# Analog_-_Low_Speed_SE.net
KiCad netlist of a schematic drawn in Altium Designer
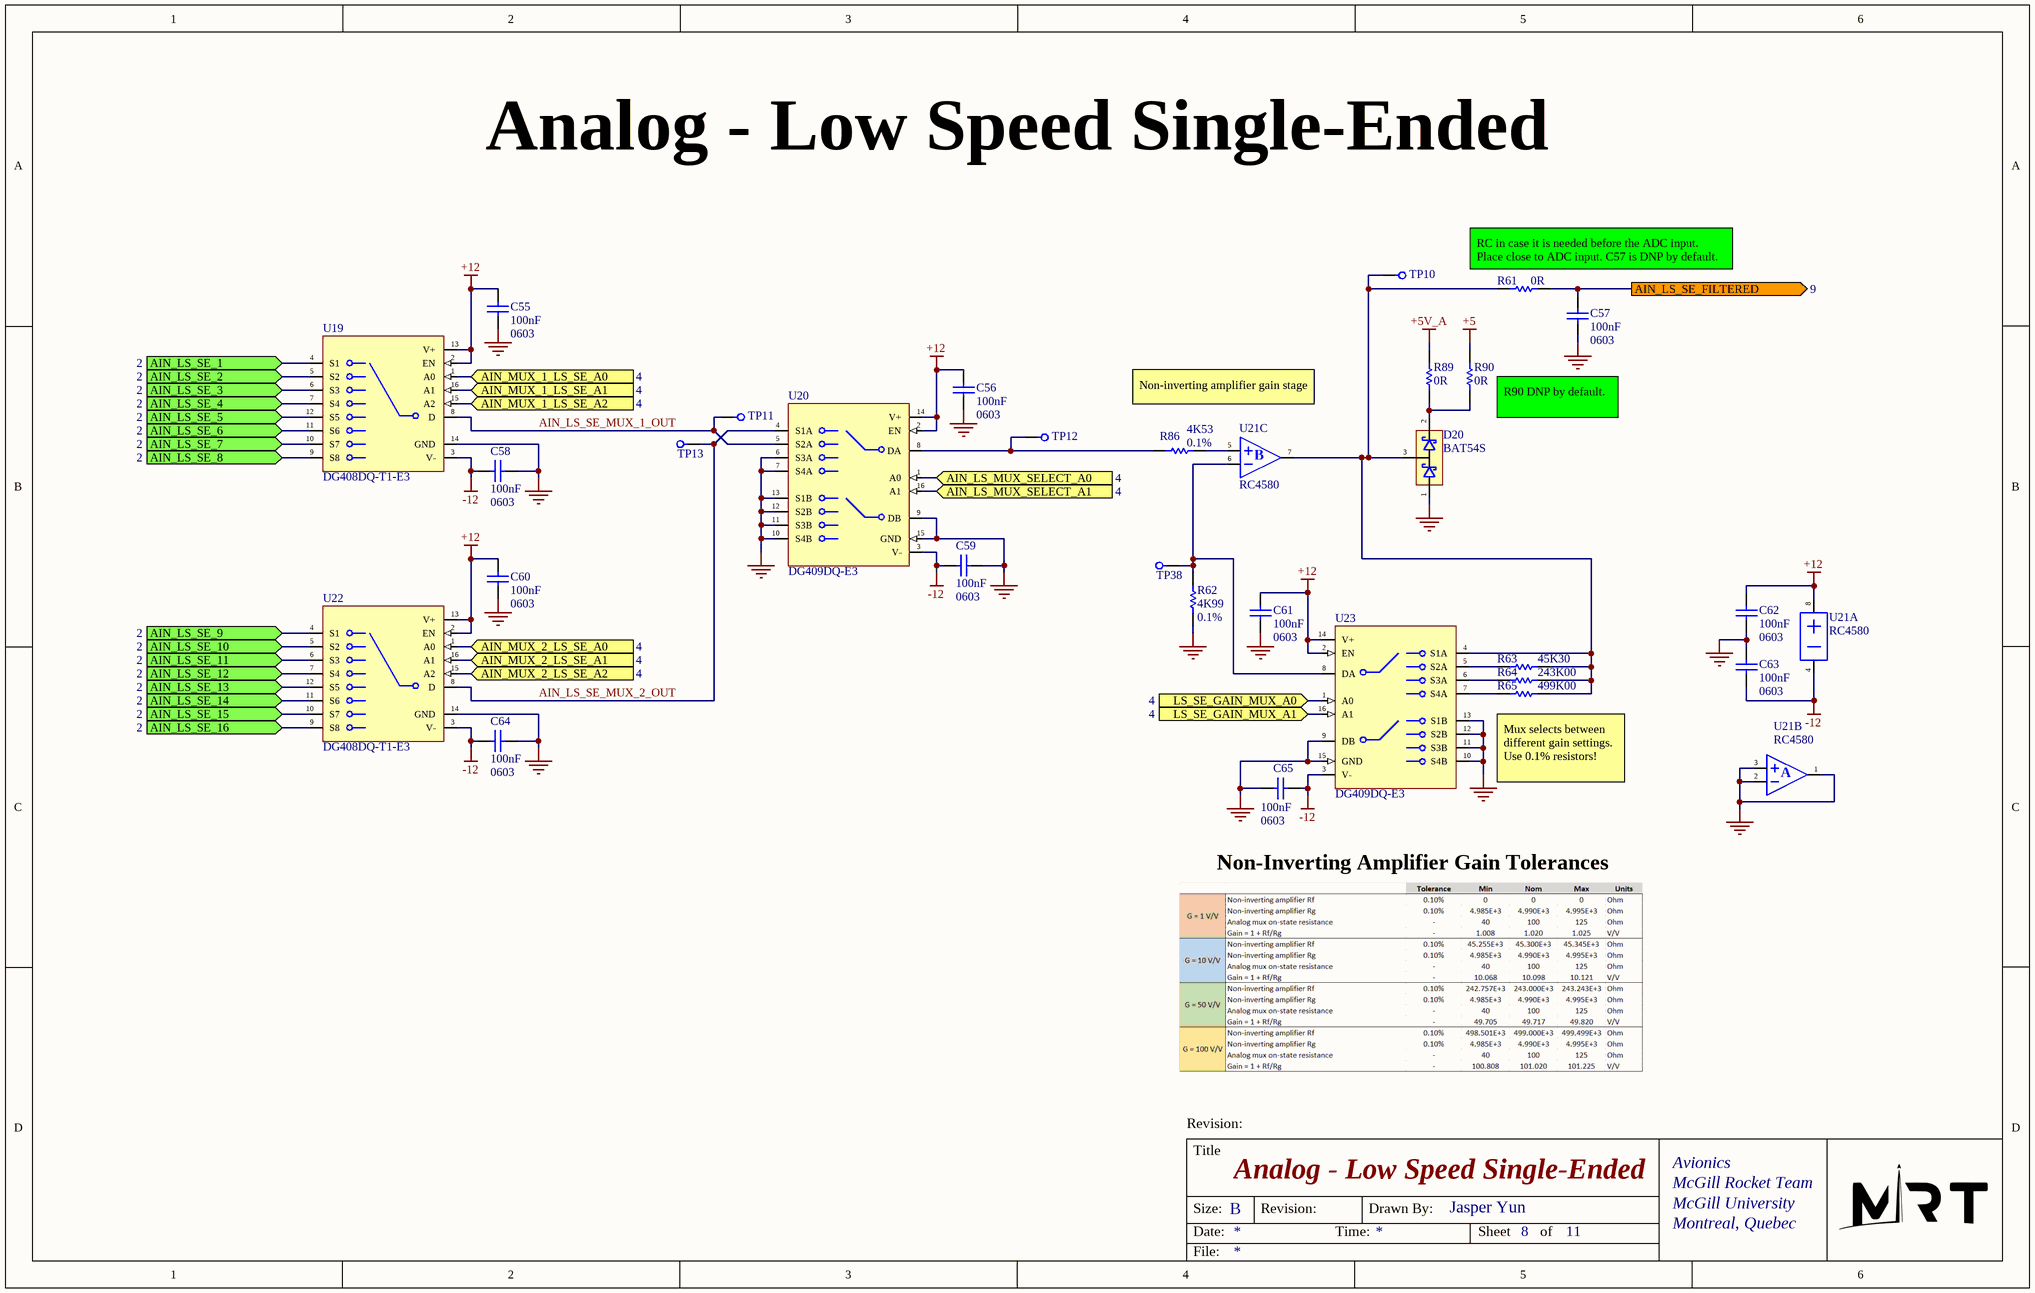
[diagram p0: Analog - Low Speed SE.SchDoc]

(export (version "E")
  (design (tool "Eeschema 10.0.6"))
  (components
    (comp (ref "C55")
      (value "100nF")
      (footprint "0603 CAP SAMSUNG CL10C")
      (description "Capacitor")
      (fields (field (name "ALTIUM_VALUE") "0603") (field (name "PUBLISHER") "Altium Limited"))
      (libsource (lib "Miscellaneous Devices") (part "Cap"))
    )
    (comp (ref "C56")
      (value "100nF")
      (footprint "0603 CAP SAMSUNG CL10C")
      (description "Capacitor")
      (fields (field (name "ALTIUM_VALUE") "0603") (field (name "PUBLISHER") "Altium Limited"))
      (libsource (lib "Miscellaneous Devices") (part "Cap"))
    )
    (comp (ref "C57")
      (value "100nF")
      (footprint "0603 CAP SAMSUNG CL10C")
      (description "Capacitor")
      (fields (field (name "ALTIUM_VALUE") "0603") (field (name "PUBLISHER") "Altium Limited"))
      (libsource (lib "Miscellaneous Devices") (part "Cap"))
    )
    (comp (ref "C58")
      (value "100nF")
      (footprint "0603 CAP SAMSUNG CL10C")
      (description "Capacitor")
      (fields (field (name "ALTIUM_VALUE") "0603") (field (name "PUBLISHER") "Altium Limited"))
      (libsource (lib "Miscellaneous Devices") (part "Cap"))
    )
    (comp (ref "C59")
      (value "100nF")
      (footprint "0603 CAP SAMSUNG CL10C")
      (description "Capacitor")
      (fields (field (name "ALTIUM_VALUE") "0603") (field (name "PUBLISHER") "Altium Limited"))
      (libsource (lib "Miscellaneous Devices") (part "Cap"))
    )
    (comp (ref "C60")
      (value "100nF")
      (footprint "0603 CAP SAMSUNG CL10C")
      (description "Capacitor")
      (fields (field (name "ALTIUM_VALUE") "0603") (field (name "PUBLISHER") "Altium Limited"))
      (libsource (lib "Miscellaneous Devices") (part "Cap"))
    )
    (comp (ref "C61")
      (value "100nF")
      (footprint "0603 CAP SAMSUNG CL10C")
      (description "Capacitor")
      (fields (field (name "ALTIUM_VALUE") "0603") (field (name "PUBLISHER") "Altium Limited"))
      (libsource (lib "Miscellaneous Devices") (part "Cap"))
    )
    (comp (ref "C62")
      (value "100nF")
      (footprint "0603 CAP SAMSUNG CL10C")
      (description "Capacitor")
      (fields (field (name "ALTIUM_VALUE") "0603") (field (name "PUBLISHER") "Altium Limited"))
      (libsource (lib "Miscellaneous Devices") (part "Cap"))
    )
    (comp (ref "C63")
      (value "100nF")
      (footprint "0603 CAP SAMSUNG CL10C")
      (description "Capacitor")
      (fields (field (name "ALTIUM_VALUE") "0603") (field (name "PUBLISHER") "Altium Limited"))
      (libsource (lib "Miscellaneous Devices") (part "Cap"))
    )
    (comp (ref "C64")
      (value "100nF")
      (footprint "0603 CAP SAMSUNG CL10C")
      (description "Capacitor")
      (fields (field (name "ALTIUM_VALUE") "0603") (field (name "PUBLISHER") "Altium Limited"))
      (libsource (lib "Miscellaneous Devices") (part "Cap"))
    )
    (comp (ref "C65")
      (value "100nF")
      (footprint "0603 CAP SAMSUNG CL10C")
      (description "Capacitor")
      (fields (field (name "ALTIUM_VALUE") "0603") (field (name "PUBLISHER") "Altium Limited"))
      (libsource (lib "Miscellaneous Devices") (part "Cap"))
    )
    (comp (ref "D20")
      (value "BAT54S")
      (footprint "SOT23-3")
      (description "Rectifier Diode Small Signal Schottky 40V 0.3A 5ns 3-Pin SOT-23 T/R")
      (fields
        (field (name "MANUFACTURER") "STMicroelectronics")
        (field (name "MANUFACTURER PART NUMBER") "BAT54SFILM")
      )
      (libsource (lib "MRT SCH Library") (part "Schottky Diode Array BAT54S"))
    )
    (comp (ref "R61")
      (value "0R")
      (footprint "0603 RES")
      (description "Resistor")
      (fields (field (name "PUBLISHER") "Altium Limited"))
      (libsource (lib "Miscellaneous Devices") (part "Res1"))
    )
    (comp (ref "R62")
      (value "4K99")
      (footprint "0603 RES")
      (description "Resistor")
      (fields (field (name "ALTIUM_VALUE") "0.1%") (field (name "PUBLISHER") "Altium Limited"))
      (libsource (lib "Miscellaneous Devices") (part "Res1"))
    )
    (comp (ref "R63")
      (value "45K30")
      (footprint "0603 RES")
      (description "Resistor")
      (fields (field (name "PUBLISHER") "Altium Limited"))
      (libsource (lib "Miscellaneous Devices") (part "Res1"))
    )
    (comp (ref "R64")
      (value "243K00")
      (footprint "0603 RES")
      (description "Resistor")
      (fields (field (name "PUBLISHER") "Altium Limited"))
      (libsource (lib "Miscellaneous Devices") (part "Res1"))
    )
    (comp (ref "R65")
      (value "499K00")
      (footprint "0603 RES")
      (description "Resistor")
      (fields (field (name "PUBLISHER") "Altium Limited"))
      (libsource (lib "Miscellaneous Devices") (part "Res1"))
    )
    (comp (ref "R86")
      (value "4K53")
      (footprint "0603 RES")
      (description "Resistor")
      (fields (field (name "ALTIUM_VALUE") "0.1%") (field (name "PUBLISHER") "Altium Limited"))
      (libsource (lib "Miscellaneous Devices") (part "Res1"))
    )
    (comp (ref "R89")
      (value "0R")
      (footprint "0603 RES")
      (description "Resistor")
      (fields (field (name "PUBLISHER") "Altium Limited"))
      (libsource (lib "Miscellaneous Devices") (part "Res1"))
    )
    (comp (ref "R90")
      (value "0R")
      (footprint "0603 RES")
      (description "Resistor")
      (fields (field (name "PUBLISHER") "Altium Limited"))
      (libsource (lib "Miscellaneous Devices") (part "Res1"))
    )
    (comp (ref "TP10")
      (value "Test Point")
      (footprint "Test Point Keystone 5015")
      (description "Keystone 5015 Test point")
      (libsource (lib "MRT SCH Library") (part "Test Point"))
    )
    (comp (ref "TP11")
      (value "Test Point")
      (footprint "TEST POINT SMD PAD")
      (description "Keystone 5015 Test point")
      (libsource (lib "MRT SCH Library") (part "Test Point"))
    )
    (comp (ref "TP12")
      (value "Test Point")
      (footprint "Test Point Keystone 5015")
      (description "Keystone 5015 Test point")
      (libsource (lib "MRT SCH Library") (part "Test Point"))
    )
    (comp (ref "TP13")
      (value "Test Point")
      (footprint "TEST POINT SMD PAD")
      (description "Keystone 5015 Test point")
      (libsource (lib "MRT SCH Library") (part "Test Point"))
    )
    (comp (ref "TP38")
      (value "Test Point")
      (footprint "Test Point Keystone 5015")
      (description "Keystone 5015 Test point")
      (libsource (lib "MRT SCH Library") (part "Test Point"))
    )
    (comp (ref "U19")
      (value "DG408DQ-T1-E3")
      (footprint "TSSOP-16")
      (description "DG408DQ-T1-E3; Multiplexer Single 8: 1; 15 V; 18 V; 24 V; 28 V; 16-Pin TSSOP")
      (fields (field (name "MANUFACTURER") "Vishay Siliconix"))
      (libsource (lib "MRT SCH Library") (part "Analog Mux DG408DQ-T1-E3"))
    )
    (comp (ref "U20")
      (value "DG409DQ-E3")
      (footprint "TSSOP-16")
      (description "DG409 Series 20 V 8-Ch/Dual 4-Ch High-Performance CMOS Analog Multiplexer")
      (fields (field (name "MANUFACTURER") "Vishay Siliconix"))
      (libsource (lib "") (part "Analog Mux DG409DQ-E3_1"))
    )
    (comp (ref "U21")
      (value "RC4580")
      (footprint "SOIC-8")
      (fields
        (field (name "MANUFACTURER") "Texas Instruments")
        (field (name "MANUFACTURER PART NUMBER") "RC4580IDR")
      )
      (libsource (lib "MRT SCH Library") (part "OP AMP RC4580"))
    )
    (comp (ref "U22")
      (value "DG408DQ-T1-E3")
      (footprint "TSSOP-16")
      (description "DG408DQ-T1-E3; Multiplexer Single 8: 1; 15 V; 18 V; 24 V; 28 V; 16-Pin TSSOP")
      (fields (field (name "MANUFACTURER") "Vishay Siliconix"))
      (libsource (lib "MRT SCH Library") (part "Analog Mux DG408DQ-T1-E3"))
    )
    (comp (ref "U23")
      (value "DG409DQ-E3")
      (footprint "TSSOP-16")
      (description "DG409 Series 20 V 8-Ch/Dual 4-Ch High-Performance CMOS Analog Multiplexer")
      (fields (field (name "MANUFACTURER") "Vishay Siliconix"))
      (libsource (lib "MRT SCH Library") (part "Analog Mux DG409DQ-E3"))
    )
  )
  (nets
    (net (code "1") (name "+5") (class "Default")
      (node (ref "R90") (pin "1") (pinfunction "1_1") (pintype "passive"))
    )
    (net (code "2") (name "+5V_A") (class "Default")
      (node (ref "R89") (pin "1") (pinfunction "1_1") (pintype "passive"))
    )
    (net (code "3") (name "+12") (class "Default")
      (node (ref "C55") (pin "2") (pinfunction "2_2") (pintype "passive"))
      (node (ref "C56") (pin "2") (pinfunction "2_2") (pintype "passive"))
      (node (ref "C60") (pin "2") (pinfunction "2_2") (pintype "passive"))
      (node (ref "C61") (pin "2") (pinfunction "2_2") (pintype "passive"))
      (node (ref "C62") (pin "2") (pinfunction "2_2") (pintype "passive"))
      (node (ref "U19") (pin "13") (pinfunction "V+_13") (pintype "passive"))
      (node (ref "U19") (pin "2") (pinfunction "EN_2") (pintype "input"))
      (node (ref "U20") (pin "14") (pinfunction "V+_14") (pintype "passive"))
      (node (ref "U20") (pin "2") (pinfunction "EN_2") (pintype "input"))
      (node (ref "U21") (pin "8") (pinfunction "VCC+_8") (pintype "passive"))
      (node (ref "U22") (pin "13") (pinfunction "V+_13") (pintype "passive"))
      (node (ref "U22") (pin "2") (pinfunction "EN_2") (pintype "input"))
      (node (ref "U23") (pin "14") (pinfunction "V+_14") (pintype "passive"))
      (node (ref "U23") (pin "2") (pinfunction "EN_2") (pintype "input"))
    )
    (net (code "4") (name "-12") (class "Default")
      (node (ref "C58") (pin "2") (pinfunction "2_2") (pintype "passive"))
      (node (ref "C59") (pin "2") (pinfunction "2_2") (pintype "passive"))
      (node (ref "C63") (pin "1") (pinfunction "1_1") (pintype "passive"))
      (node (ref "C64") (pin "2") (pinfunction "2_2") (pintype "passive"))
      (node (ref "C65") (pin "2") (pinfunction "2_2") (pintype "passive"))
      (node (ref "U19") (pin "3") (pinfunction "V-_3") (pintype "passive"))
      (node (ref "U20") (pin "3") (pinfunction "V-_3") (pintype "passive"))
      (node (ref "U21") (pin "4") (pinfunction "VCC-_4") (pintype "passive"))
      (node (ref "U22") (pin "3") (pinfunction "V-_3") (pintype "passive"))
      (node (ref "U23") (pin "3") (pinfunction "V-_3") (pintype "passive"))
    )
    (net (code "5") (name "/AIN_LS_MUX_SELECT_A0") (class "Default")
      (node (ref "U20") (pin "1") (pinfunction "A0_1") (pintype "input"))
    )
    (net (code "6") (name "/AIN_LS_MUX_SELECT_A1") (class "Default")
      (node (ref "U20") (pin "16") (pinfunction "A1_16") (pintype "input"))
    )
    (net (code "7") (name "/AIN_LS_SE_1") (class "Default")
      (node (ref "U19") (pin "4") (pinfunction "S1_4") (pintype "passive"))
    )
    (net (code "8") (name "/AIN_LS_SE_2") (class "Default")
      (node (ref "U19") (pin "5") (pinfunction "S2_5") (pintype "passive"))
    )
    (net (code "9") (name "/AIN_LS_SE_3") (class "Default")
      (node (ref "U19") (pin "6") (pinfunction "S3_6") (pintype "passive"))
    )
    (net (code "10") (name "/AIN_LS_SE_4") (class "Default")
      (node (ref "U19") (pin "7") (pinfunction "S4_7") (pintype "passive"))
    )
    (net (code "11") (name "/AIN_LS_SE_5") (class "Default")
      (node (ref "U19") (pin "12") (pinfunction "S5_12") (pintype "passive"))
    )
    (net (code "12") (name "/AIN_LS_SE_6") (class "Default")
      (node (ref "U19") (pin "11") (pinfunction "S6_11") (pintype "passive"))
    )
    (net (code "13") (name "/AIN_LS_SE_7") (class "Default")
      (node (ref "U19") (pin "10") (pinfunction "S7_10") (pintype "passive"))
    )
    (net (code "14") (name "/AIN_LS_SE_8") (class "Default")
      (node (ref "U19") (pin "9") (pinfunction "S8_9") (pintype "passive"))
    )
    (net (code "15") (name "/AIN_LS_SE_9") (class "Default")
      (node (ref "U22") (pin "4") (pinfunction "S1_4") (pintype "passive"))
    )
    (net (code "16") (name "/AIN_LS_SE_10") (class "Default")
      (node (ref "U22") (pin "5") (pinfunction "S2_5") (pintype "passive"))
    )
    (net (code "17") (name "/AIN_LS_SE_11") (class "Default")
      (node (ref "U22") (pin "6") (pinfunction "S3_6") (pintype "passive"))
    )
    (net (code "18") (name "/AIN_LS_SE_12") (class "Default")
      (node (ref "U22") (pin "7") (pinfunction "S4_7") (pintype "passive"))
    )
    (net (code "19") (name "/AIN_LS_SE_13") (class "Default")
      (node (ref "U22") (pin "12") (pinfunction "S5_12") (pintype "passive"))
    )
    (net (code "20") (name "/AIN_LS_SE_14") (class "Default")
      (node (ref "U22") (pin "11") (pinfunction "S6_11") (pintype "passive"))
    )
    (net (code "21") (name "/AIN_LS_SE_15") (class "Default")
      (node (ref "U22") (pin "10") (pinfunction "S7_10") (pintype "passive"))
    )
    (net (code "22") (name "/AIN_LS_SE_16") (class "Default")
      (node (ref "U22") (pin "9") (pinfunction "S8_9") (pintype "passive"))
    )
    (net (code "23") (name "/AIN_LS_SE_FILTERED") (class "Default")
      (node (ref "C57") (pin "2") (pinfunction "2_2") (pintype "passive"))
      (node (ref "R61") (pin "1") (pinfunction "1_1") (pintype "passive"))
    )
    (net (code "24") (name "/AIN_LS_SE_MUX_1_OUT") (class "Default")
      (node (ref "TP11") (pin "1") (pinfunction "1_1") (pintype "passive"))
      (node (ref "U19") (pin "8") (pinfunction "D_8") (pintype "passive"))
      (node (ref "U20") (pin "5") (pinfunction "S2A_5") (pintype "passive"))
    )
    (net (code "25") (name "/AIN_LS_SE_MUX_2_OUT") (class "Default")
      (node (ref "TP13") (pin "1") (pinfunction "1_1") (pintype "passive"))
      (node (ref "U20") (pin "4") (pinfunction "S1A_4") (pintype "passive"))
      (node (ref "U22") (pin "8") (pinfunction "D_8") (pintype "passive"))
    )
    (net (code "26") (name "/AIN_MUX_1_LS_SE_A0") (class "Default")
      (node (ref "U19") (pin "1") (pinfunction "A0_1") (pintype "input"))
    )
    (net (code "27") (name "/AIN_MUX_1_LS_SE_A1") (class "Default")
      (node (ref "U19") (pin "16") (pinfunction "A1_16") (pintype "input"))
    )
    (net (code "28") (name "/AIN_MUX_1_LS_SE_A2") (class "Default")
      (node (ref "U19") (pin "15") (pinfunction "A2_15") (pintype "input"))
    )
    (net (code "29") (name "/AIN_MUX_2_LS_SE_A0") (class "Default")
      (node (ref "U22") (pin "1") (pinfunction "A0_1") (pintype "input"))
    )
    (net (code "30") (name "/AIN_MUX_2_LS_SE_A1") (class "Default")
      (node (ref "U22") (pin "16") (pinfunction "A1_16") (pintype "input"))
    )
    (net (code "31") (name "/AIN_MUX_2_LS_SE_A2") (class "Default")
      (node (ref "U22") (pin "15") (pinfunction "A2_15") (pintype "input"))
    )
    (net (code "32") (name "/LS_SE_GAIN_MUX_A0") (class "Default")
      (node (ref "U23") (pin "1") (pinfunction "A0_1") (pintype "input"))
    )
    (net (code "33") (name "/LS_SE_GAIN_MUX_A1") (class "Default")
      (node (ref "U23") (pin "16") (pinfunction "A1_16") (pintype "input"))
    )
    (net (code "34") (name "GND") (class "Default")
      (node (ref "C55") (pin "1") (pinfunction "1_1") (pintype "passive"))
      (node (ref "C56") (pin "1") (pinfunction "1_1") (pintype "passive"))
      (node (ref "C57") (pin "1") (pinfunction "1_1") (pintype "passive"))
      (node (ref "C58") (pin "1") (pinfunction "1_1") (pintype "passive"))
      (node (ref "C59") (pin "1") (pinfunction "1_1") (pintype "passive"))
      (node (ref "C60") (pin "1") (pinfunction "1_1") (pintype "passive"))
      (node (ref "C61") (pin "1") (pinfunction "1_1") (pintype "passive"))
      (node (ref "C62") (pin "1") (pinfunction "1_1") (pintype "passive"))
      (node (ref "C63") (pin "2") (pinfunction "2_2") (pintype "passive"))
      (node (ref "C64") (pin "1") (pinfunction "1_1") (pintype "passive"))
      (node (ref "C65") (pin "1") (pinfunction "1_1") (pintype "passive"))
      (node (ref "D20") (pin "1") (pinfunction "1_1") (pintype "passive"))
      (node (ref "R62") (pin "1") (pinfunction "1_1") (pintype "passive"))
      (node (ref "U19") (pin "14") (pinfunction "GND_14") (pintype "passive"))
      (node (ref "U20") (pin "10") (pinfunction "S4B_10") (pintype "passive"))
      (node (ref "U20") (pin "11") (pinfunction "S3B_11") (pintype "passive"))
      (node (ref "U20") (pin "12") (pinfunction "S2B_12") (pintype "passive"))
      (node (ref "U20") (pin "13") (pinfunction "S1B_13") (pintype "passive"))
      (node (ref "U20") (pin "15") (pinfunction "GND_15") (pintype "input"))
      (node (ref "U20") (pin "6") (pinfunction "S3A_6") (pintype "passive"))
      (node (ref "U20") (pin "7") (pinfunction "S4A_7") (pintype "passive"))
      (node (ref "U20") (pin "9") (pinfunction "DB_9") (pintype "passive"))
      (node (ref "U21") (pin "1") (pinfunction "1_1") (pintype "passive"))
      (node (ref "U21") (pin "2") (pinfunction "2_2") (pintype "passive"))
      (node (ref "U21") (pin "3") (pinfunction "3_3") (pintype "passive"))
      (node (ref "U22") (pin "14") (pinfunction "GND_14") (pintype "passive"))
      (node (ref "U23") (pin "10") (pinfunction "S4B_10") (pintype "passive"))
      (node (ref "U23") (pin "11") (pinfunction "S3B_11") (pintype "passive"))
      (node (ref "U23") (pin "12") (pinfunction "S2B_12") (pintype "passive"))
      (node (ref "U23") (pin "13") (pinfunction "S1B_13") (pintype "passive"))
      (node (ref "U23") (pin "15") (pinfunction "GND_15") (pintype "input"))
      (node (ref "U23") (pin "9") (pinfunction "DB_9") (pintype "passive"))
    )
    (net (code "35") (name "Net-(D20-Pad2)") (class "Default")
      (node (ref "D20") (pin "2") (pinfunction "2_2") (pintype "passive"))
      (node (ref "R89") (pin "2") (pinfunction "2_2") (pintype "passive"))
      (node (ref "R90") (pin "2") (pinfunction "2_2") (pintype "passive"))
    )
    (net (code "36") (name "Net-(R86-Pad1)") (class "Default")
      (node (ref "R86") (pin "1") (pinfunction "1_1") (pintype "passive"))
      (node (ref "U21") (pin "5") (pinfunction "5_5") (pintype "passive"))
    )
    (net (code "37") (name "Net-(U20-DA)") (class "Default")
      (node (ref "R86") (pin "2") (pinfunction "2_2") (pintype "passive"))
      (node (ref "TP12") (pin "1") (pinfunction "1_1") (pintype "passive"))
      (node (ref "U20") (pin "8") (pinfunction "DA_8") (pintype "passive"))
    )
    (net (code "38") (name "Net-(U23-DA)") (class "Default")
      (node (ref "R62") (pin "2") (pinfunction "2_2") (pintype "passive"))
      (node (ref "TP38") (pin "1") (pinfunction "1_1") (pintype "passive"))
      (node (ref "U21") (pin "6") (pinfunction "6_6") (pintype "passive"))
      (node (ref "U23") (pin "8") (pinfunction "DA_8") (pintype "passive"))
    )
    (net (code "39") (name "Net-(U23-S1A)") (class "Default")
      (node (ref "D20") (pin "3") (pinfunction "3_3") (pintype "passive"))
      (node (ref "R61") (pin "2") (pinfunction "2_2") (pintype "passive"))
      (node (ref "R63") (pin "1") (pinfunction "1_1") (pintype "passive"))
      (node (ref "R64") (pin "1") (pinfunction "1_1") (pintype "passive"))
      (node (ref "R65") (pin "1") (pinfunction "1_1") (pintype "passive"))
      (node (ref "TP10") (pin "1") (pinfunction "1_1") (pintype "passive"))
      (node (ref "U21") (pin "7") (pinfunction "7_7") (pintype "passive"))
      (node (ref "U23") (pin "4") (pinfunction "S1A_4") (pintype "passive"))
    )
    (net (code "40") (name "Net-(U23-S2A)") (class "Default")
      (node (ref "R63") (pin "2") (pinfunction "2_2") (pintype "passive"))
      (node (ref "U23") (pin "5") (pinfunction "S2A_5") (pintype "passive"))
    )
    (net (code "41") (name "Net-(U23-S3A)") (class "Default")
      (node (ref "R64") (pin "2") (pinfunction "2_2") (pintype "passive"))
      (node (ref "U23") (pin "6") (pinfunction "S3A_6") (pintype "passive"))
    )
    (net (code "42") (name "Net-(U23-S4A)") (class "Default")
      (node (ref "R65") (pin "2") (pinfunction "2_2") (pintype "passive"))
      (node (ref "U23") (pin "7") (pinfunction "S4A_7") (pintype "passive"))
    )
  )
)
